# LazuriteMiniDongle3.net
KiCad netlist of a schematic drawn in EAGLE
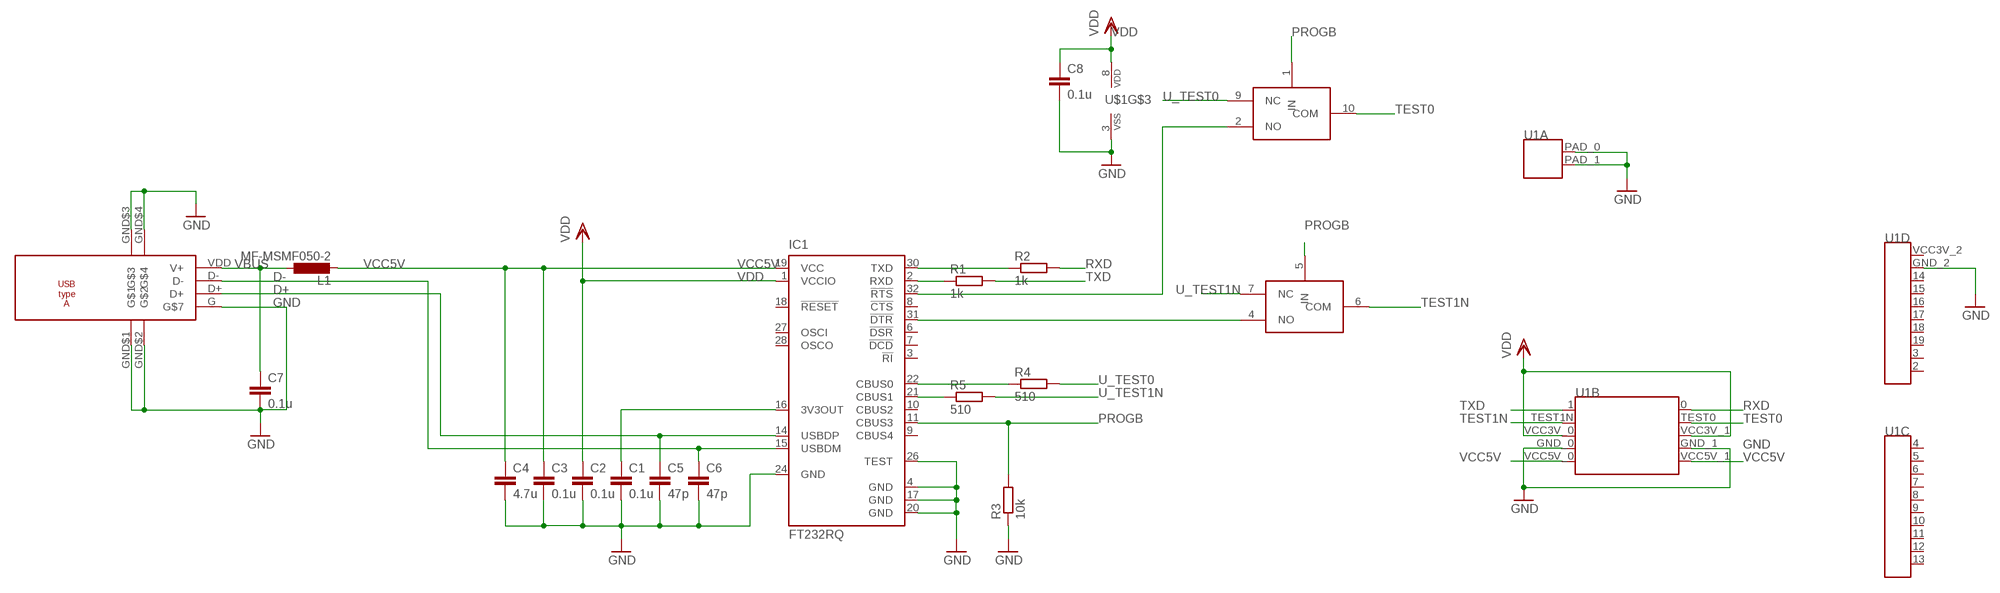
[diagram p0: schematic, sheet 1]

(export (version "E")
  (design (tool "Eeschema 10.0.6"))
  (components
    (comp (ref "C1")
      (value "0.1u")
      (footprint "eagle-import:C0402")
      (libsource (lib "eagle-import") (part "C-EUC0402"))
    )
    (comp (ref "C2")
      (value "0.1u")
      (footprint "eagle-import:C0402")
      (libsource (lib "eagle-import") (part "C-EUC0402"))
    )
    (comp (ref "C3")
      (value "0.1u")
      (footprint "eagle-import:C0402")
      (libsource (lib "eagle-import") (part "C-EUC0402"))
    )
    (comp (ref "C4")
      (value "4.7u")
      (footprint "eagle-import:C1608")
      (libsource (lib "eagle-import") (part "resistor_C-EUC1608"))
    )
    (comp (ref "C5")
      (value "47p")
      (footprint "eagle-import:C0402")
      (libsource (lib "eagle-import") (part "C-EUC0402"))
    )
    (comp (ref "C6")
      (value "47p")
      (footprint "eagle-import:C0402")
      (libsource (lib "eagle-import") (part "C-EUC0402"))
    )
    (comp (ref "C7")
      (value "0.1u")
      (footprint "eagle-import:C0402")
      (libsource (lib "eagle-import") (part "C-EUC0402"))
    )
    (comp (ref "C8")
      (value "0.1u")
      (footprint "eagle-import:C0402")
      (libsource (lib "eagle-import") (part "C-EUC0402"))
    )
    (comp (ref "IC1")
      (value "FT232RQ")
      (footprint "eagle-import:QFN32")
      (libsource (lib "eagle-import") (part "FT232RQ"))
    )
    (comp (ref "L1")
      (value "MF-MSMF050-2")
      (footprint "eagle-import:L1812")
      (libsource (lib "eagle-import") (part "L-EUL1812"))
    )
    (comp (ref "R1")
      (value "1k")
      (footprint "eagle-import:R0402")
      (libsource (lib "eagle-import") (part "R-EU_R0402"))
    )
    (comp (ref "R2")
      (value "1k")
      (footprint "eagle-import:R0402")
      (libsource (lib "eagle-import") (part "R-EU_R0402"))
    )
    (comp (ref "R3")
      (value "10k")
      (footprint "eagle-import:R0402")
      (libsource (lib "eagle-import") (part "R-EU_R0402"))
    )
    (comp (ref "R4")
      (value "510")
      (footprint "eagle-import:R0402")
      (libsource (lib "eagle-import") (part "R-EU_R0402"))
    )
    (comp (ref "R5")
      (value "510")
      (footprint "eagle-import:R0402")
      (libsource (lib "eagle-import") (part "R-EU_R0402"))
    )
    (comp (ref "U$1")
      (value "TI-TS5A23159")
      (footprint "eagle-import:UQFN10")
      (libsource (lib "eagle-import") (part "TI-TS5A23159"))
    )
    (comp (ref "U$2")
      (value "USB-TYPE-A")
      (footprint "eagle-import:UP2-AH-TH")
      (libsource (lib "eagle-import") (part "USB-TYPE-A"))
    )
    (comp (ref "U1")
      (value "LAZURITE920JNOSILK")
      (footprint "eagle-import:LAZURITE920J(NOSILK)")
      (libsource (lib "eagle-import") (part "LAZURITE920JNOSILK"))
    )
  )
  (nets
    (net (code "1") (name "/D+") (class "Default")
      (node (ref "C5") (pin "1") (pinfunction "1_1") (pintype "passive"))
      (node (ref "IC1") (pin "14") (pinfunction "USBDP_14") (pintype "bidirectional"))
      (node (ref "U$2") (pin "D+") (pinfunction "D+_D+") (pintype "bidirectional"))
    )
    (net (code "2") (name "/D-") (class "Default")
      (node (ref "C6") (pin "1") (pinfunction "1_1") (pintype "passive"))
      (node (ref "IC1") (pin "15") (pinfunction "USBDM_15") (pintype "bidirectional"))
      (node (ref "U$2") (pin "D-") (pinfunction "D-_D-") (pintype "bidirectional"))
    )
    (net (code "3") (name "/PROGB") (class "Default")
      (node (ref "IC1") (pin "11") (pinfunction "CBUS3_11") (pintype "bidirectional"))
      (node (ref "R3") (pin "2") (pinfunction "2_2") (pintype "passive"))
      (node (ref "U$1") (pin "1") (pinfunction "IN_1") (pintype "bidirectional"))
      (node (ref "U$1") (pin "5") (pinfunction "IN_5") (pintype "bidirectional"))
    )
    (net (code "4") (name "/RXD") (class "Default")
      (node (ref "R2") (pin "2") (pinfunction "2_2") (pintype "passive"))
      (node (ref "U1") (pin "0") (pinfunction "0_0") (pintype "passive"))
    )
    (net (code "5") (name "/TEST0") (class "Default")
      (node (ref "U$1") (pin "10") (pinfunction "COM_10") (pintype "bidirectional"))
      (node (ref "U1") (pin "TEST0") (pinfunction "TEST0_TEST0") (pintype "passive"))
    )
    (net (code "6") (name "/TEST1N") (class "Default")
      (node (ref "U$1") (pin "6") (pinfunction "COM_6") (pintype "bidirectional"))
      (node (ref "U1") (pin "TEST1N") (pinfunction "TEST1N_TEST1N") (pintype "passive"))
    )
    (net (code "7") (name "/TXD") (class "Default")
      (node (ref "R1") (pin "2") (pinfunction "2_2") (pintype "passive"))
      (node (ref "U1") (pin "1") (pinfunction "1_1") (pintype "passive"))
    )
    (net (code "8") (name "/U_TEST0") (class "Default")
      (node (ref "R4") (pin "2") (pinfunction "2_2") (pintype "passive"))
      (node (ref "U$1") (pin "9") (pinfunction "NC_9") (pintype "bidirectional"))
    )
    (net (code "9") (name "/U_TEST1N") (class "Default")
      (node (ref "R5") (pin "2") (pinfunction "2_2") (pintype "passive"))
      (node (ref "U$1") (pin "7") (pinfunction "NC_7") (pintype "bidirectional"))
    )
    (net (code "10") (name "/VBUS") (class "Default")
      (node (ref "C7") (pin "1") (pinfunction "1_1") (pintype "passive"))
      (node (ref "L1") (pin "1") (pinfunction "1_1") (pintype "passive"))
      (node (ref "U$2") (pin "VDD") (pinfunction "V+_VDD") (pintype "bidirectional"))
    )
    (net (code "11") (name "/VCC5V") (class "Default")
      (node (ref "C3") (pin "1") (pinfunction "1_1") (pintype "passive"))
      (node (ref "C4") (pin "1") (pinfunction "1_1") (pintype "passive"))
      (node (ref "IC1") (pin "19") (pinfunction "VCC_19") (pintype "power_in"))
      (node (ref "L1") (pin "2") (pinfunction "2_2") (pintype "passive"))
      (node (ref "U1") (pin "VCC5V_0") (pinfunction "VCC5V_0_VCC5V_0") (pintype "passive"))
      (node (ref "U1") (pin "VCC5V_1") (pinfunction "VCC5V_1_VCC5V_1") (pintype "passive"))
    )
    (net (code "12") (name "GND") (class "Default")
      (node (ref "C1") (pin "2") (pinfunction "2_2") (pintype "passive"))
      (node (ref "C2") (pin "2") (pinfunction "2_2") (pintype "passive"))
      (node (ref "C3") (pin "2") (pinfunction "2_2") (pintype "passive"))
      (node (ref "C4") (pin "2") (pinfunction "2_2") (pintype "passive"))
      (node (ref "C5") (pin "2") (pinfunction "2_2") (pintype "passive"))
      (node (ref "C6") (pin "2") (pinfunction "2_2") (pintype "passive"))
      (node (ref "C7") (pin "2") (pinfunction "2_2") (pintype "passive"))
      (node (ref "C8") (pin "2") (pinfunction "2_2") (pintype "passive"))
      (node (ref "IC1") (pin "17") (pinfunction "GND_17") (pintype "power_in"))
      (node (ref "IC1") (pin "20") (pinfunction "GND_20") (pintype "power_in"))
      (node (ref "IC1") (pin "24") (pinfunction "GND_24") (pintype "power_in"))
      (node (ref "IC1") (pin "26") (pinfunction "TEST_26") (pintype "input"))
      (node (ref "IC1") (pin "4") (pinfunction "GND_4") (pintype "power_in"))
      (node (ref "R3") (pin "1") (pinfunction "1_1") (pintype "passive"))
      (node (ref "U$1") (pin "3") (pinfunction "VSS_3") (pintype "power_in"))
      (node (ref "U$2") (pin "G") (pinfunction "G$7_G") (pintype "power_in"))
      (node (ref "U$2") (pin "GND$1") (pinfunction "G$1_GND$1") (pintype "power_in"))
      (node (ref "U$2") (pin "GND$2") (pinfunction "G$2_GND$2") (pintype "power_in"))
      (node (ref "U$2") (pin "GND$3") (pinfunction "G$3_GND$3") (pintype "power_in"))
      (node (ref "U$2") (pin "GND$4") (pinfunction "G$4_GND$4") (pintype "power_in"))
      (node (ref "U1") (pin "GND_0") (pinfunction "GND_0_GND_0") (pintype "passive"))
      (node (ref "U1") (pin "GND_1") (pinfunction "GND_1_GND_1") (pintype "passive"))
      (node (ref "U1") (pin "GND_2") (pinfunction "GND_2_GND_2") (pintype "passive"))
      (node (ref "U1") (pin "PAD_0") (pinfunction "PAD_0_PAD_0") (pintype "passive"))
      (node (ref "U1") (pin "PAD_1") (pinfunction "PAD_1_PAD_1") (pintype "passive"))
    )
    (net (code "13") (name "Net-(IC1-3V3OUT)") (class "Default")
      (node (ref "C1") (pin "1") (pinfunction "1_1") (pintype "passive"))
      (node (ref "IC1") (pin "16") (pinfunction "3V3OUT_16") (pintype "output"))
    )
    (net (code "14") (name "Net-(IC1-CBUS0)") (class "Default")
      (node (ref "IC1") (pin "22") (pinfunction "CBUS0_22") (pintype "bidirectional"))
      (node (ref "R4") (pin "1") (pinfunction "1_1") (pintype "passive"))
    )
    (net (code "15") (name "Net-(IC1-CBUS1)") (class "Default")
      (node (ref "IC1") (pin "21") (pinfunction "CBUS1_21") (pintype "bidirectional"))
      (node (ref "R5") (pin "1") (pinfunction "1_1") (pintype "passive"))
    )
    (net (code "16") (name "Net-(IC1-RXD)") (class "Default")
      (node (ref "IC1") (pin "2") (pinfunction "RXD_2") (pintype "input"))
      (node (ref "R1") (pin "1") (pinfunction "1_1") (pintype "passive"))
    )
    (net (code "17") (name "Net-(IC1-TXD)") (class "Default")
      (node (ref "IC1") (pin "30") (pinfunction "TXD_30") (pintype "output"))
      (node (ref "R2") (pin "1") (pinfunction "1_1") (pintype "passive"))
    )
    (net (code "18") (name "Net-(IC1-~{DTR})") (class "Default")
      (node (ref "IC1") (pin "31") (pinfunction "~{DTR}_31") (pintype "output"))
      (node (ref "U$1") (pin "4") (pinfunction "NO_4") (pintype "bidirectional"))
    )
    (net (code "19") (name "Net-(IC1-~{RTS})") (class "Default")
      (node (ref "IC1") (pin "32") (pinfunction "~{RTS}_32") (pintype "output"))
      (node (ref "U$1") (pin "2") (pinfunction "NO_2") (pintype "bidirectional"))
    )
    (net (code "20") (name "VDD") (class "Default")
      (node (ref "C2") (pin "1") (pinfunction "1_1") (pintype "passive"))
      (node (ref "C8") (pin "1") (pinfunction "1_1") (pintype "passive"))
      (node (ref "IC1") (pin "1") (pinfunction "VCCIO_1") (pintype "power_in"))
      (node (ref "U$1") (pin "8") (pinfunction "VDD_8") (pintype "power_in"))
      (node (ref "U1") (pin "VCC3V_0") (pinfunction "VCC3V_0_VCC3V_0") (pintype "passive"))
      (node (ref "U1") (pin "VCC3V_1") (pinfunction "VCC3V_1_VCC3V_1") (pintype "passive"))
    )
    (net (code "21") (name "unconnected-(IC1-CBUS2-Pad10)") (class "Default")
      (node (ref "IC1") (pin "10") (pinfunction "CBUS2_10") (pintype "bidirectional"))
    )
    (net (code "22") (name "unconnected-(IC1-CBUS4-Pad9)") (class "Default")
      (node (ref "IC1") (pin "9") (pinfunction "CBUS4_9") (pintype "bidirectional"))
    )
    (net (code "23") (name "unconnected-(IC1-OSCI-Pad27)") (class "Default")
      (node (ref "IC1") (pin "27") (pinfunction "OSCI_27") (pintype "input"))
    )
    (net (code "24") (name "unconnected-(IC1-OSCO-Pad28)") (class "Default")
      (node (ref "IC1") (pin "28") (pinfunction "OSCO_28") (pintype "output"))
    )
    (net (code "25") (name "unconnected-(IC1-~{CTS}-Pad8)") (class "Default")
      (node (ref "IC1") (pin "8") (pinfunction "~{CTS}_8") (pintype "input"))
    )
    (net (code "26") (name "unconnected-(IC1-~{DCD}-Pad7)") (class "Default")
      (node (ref "IC1") (pin "7") (pinfunction "~{DCD}_7") (pintype "input"))
    )
    (net (code "27") (name "unconnected-(IC1-~{DSR}-Pad6)") (class "Default")
      (node (ref "IC1") (pin "6") (pinfunction "~{DSR}_6") (pintype "input"))
    )
    (net (code "28") (name "unconnected-(IC1-~{RESET}-Pad18)") (class "Default")
      (node (ref "IC1") (pin "18") (pinfunction "~{RESET}_18") (pintype "input"))
    )
    (net (code "29") (name "unconnected-(IC1-~{RI}-Pad3)") (class "Default")
      (node (ref "IC1") (pin "3") (pinfunction "~{RI}_3") (pintype "input"))
    )
    (net (code "30") (name "unconnected-(U1-Pad2)") (class "Default")
      (node (ref "U1") (pin "2") (pinfunction "2_2") (pintype "passive"))
    )
    (net (code "31") (name "unconnected-(U1-Pad3)") (class "Default")
      (node (ref "U1") (pin "3") (pinfunction "3_3") (pintype "passive"))
    )
    (net (code "32") (name "unconnected-(U1-Pad4)") (class "Default")
      (node (ref "U1") (pin "4") (pinfunction "4_4") (pintype "passive"))
    )
    (net (code "33") (name "unconnected-(U1-Pad5)") (class "Default")
      (node (ref "U1") (pin "5") (pinfunction "5_5") (pintype "passive"))
    )
    (net (code "34") (name "unconnected-(U1-Pad6)") (class "Default")
      (node (ref "U1") (pin "6") (pinfunction "6_6") (pintype "passive"))
    )
    (net (code "35") (name "unconnected-(U1-Pad7)") (class "Default")
      (node (ref "U1") (pin "7") (pinfunction "7_7") (pintype "passive"))
    )
    (net (code "36") (name "unconnected-(U1-Pad8)") (class "Default")
      (node (ref "U1") (pin "8") (pinfunction "8_8") (pintype "passive"))
    )
    (net (code "37") (name "unconnected-(U1-Pad9)") (class "Default")
      (node (ref "U1") (pin "9") (pinfunction "9_9") (pintype "passive"))
    )
    (net (code "38") (name "unconnected-(U1-Pad10)") (class "Default")
      (node (ref "U1") (pin "10") (pinfunction "10_10") (pintype "passive"))
    )
    (net (code "39") (name "unconnected-(U1-Pad11)") (class "Default")
      (node (ref "U1") (pin "11") (pinfunction "11_11") (pintype "passive"))
    )
    (net (code "40") (name "unconnected-(U1-Pad12)") (class "Default")
      (node (ref "U1") (pin "12") (pinfunction "12_12") (pintype "passive"))
    )
    (net (code "41") (name "unconnected-(U1-Pad13)") (class "Default")
      (node (ref "U1") (pin "13") (pinfunction "13_13") (pintype "passive"))
    )
    (net (code "42") (name "unconnected-(U1-Pad14)") (class "Default")
      (node (ref "U1") (pin "14") (pinfunction "14_14") (pintype "passive"))
    )
    (net (code "43") (name "unconnected-(U1-Pad15)") (class "Default")
      (node (ref "U1") (pin "15") (pinfunction "15_15") (pintype "passive"))
    )
    (net (code "44") (name "unconnected-(U1-Pad16)") (class "Default")
      (node (ref "U1") (pin "16") (pinfunction "16_16") (pintype "passive"))
    )
    (net (code "45") (name "unconnected-(U1-Pad17)") (class "Default")
      (node (ref "U1") (pin "17") (pinfunction "17_17") (pintype "passive"))
    )
    (net (code "46") (name "unconnected-(U1-Pad18)") (class "Default")
      (node (ref "U1") (pin "18") (pinfunction "18_18") (pintype "passive"))
    )
    (net (code "47") (name "unconnected-(U1-Pad19)") (class "Default")
      (node (ref "U1") (pin "19") (pinfunction "19_19") (pintype "passive"))
    )
    (net (code "48") (name "unconnected-(U1-PadVCC3V_2)") (class "Default")
      (node (ref "U1") (pin "VCC3V_2") (pinfunction "VCC3V_2_VCC3V_2") (pintype "passive"))
    )
  )
)
